# placa_v22.net
KiCad netlist of a schematic drawn in EAGLE
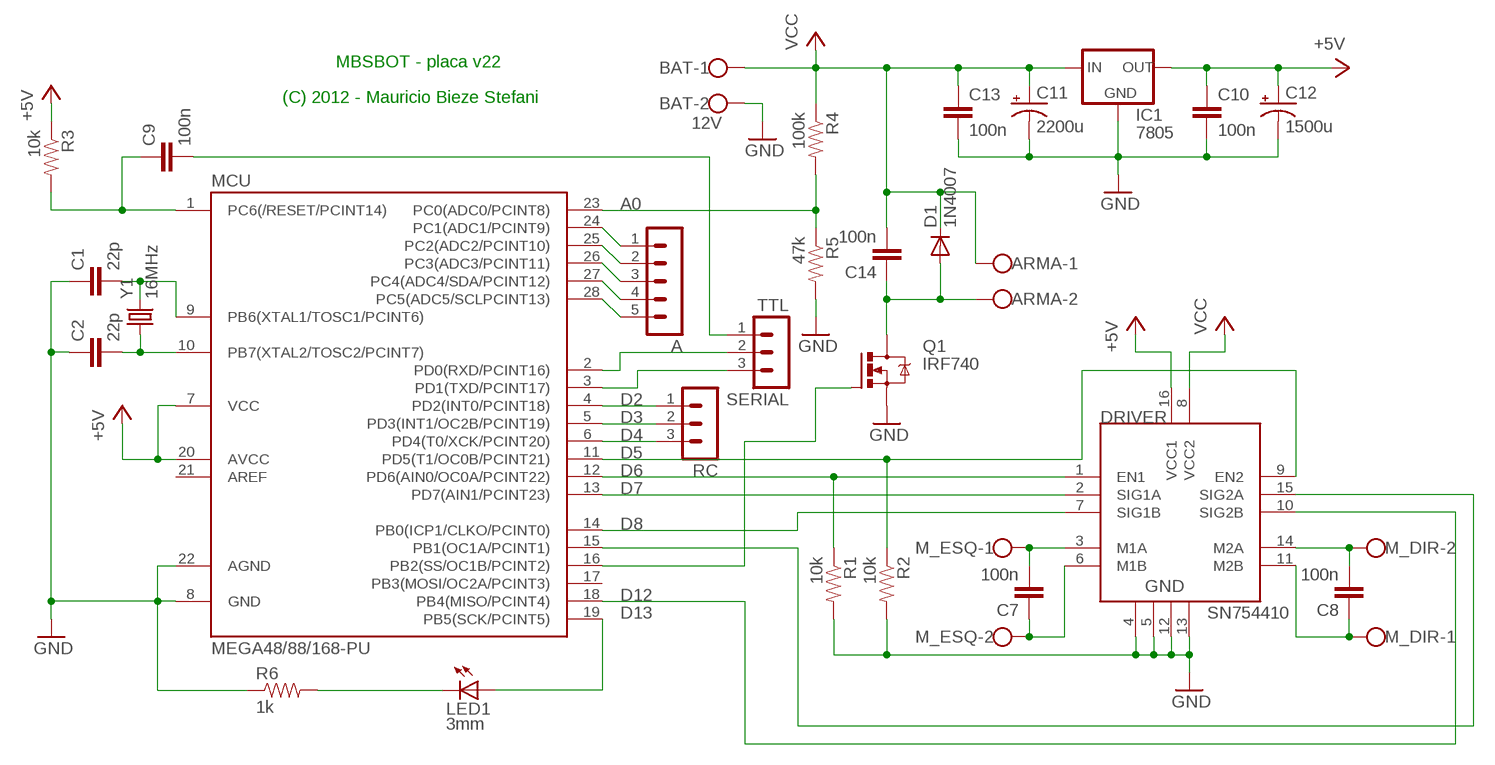
[diagram p0: schematic, sheet 1]

(export (version "E")
  (design (tool "Eeschema 10.0.6"))
  (components
    (comp (ref "A")
      (value "MA05-1")
      (footprint "eagle-import:MA05-1")
      (libsource (lib "eagle-import") (part "MA05-1"))
    )
    (comp (ref "ARMA")
      (value "W237-102")
      (footprint "eagle-import:W237-102")
      (fields (field (name "MPN") "237-102"))
      (libsource (lib "eagle-import") (part "W237-102"))
    )
    (comp (ref "BAT")
      (value "12V")
      (footprint "eagle-import:W237-102")
      (fields
        (field (name "MPN") "237-102")
        (field (name "MPN_1") "237-102")
        (field (name "OC_FARNELL") "unknown")
        (field (name "OC_NEWARK") "70K9898")
      )
      (libsource (lib "eagle-import") (part "W237-102"))
    )
    (comp (ref "C1")
      (value "22p")
      (footprint "eagle-import:CAP-PTH-SMALL-KIT")
      (libsource (lib "eagle-import") (part "CAPKIT"))
    )
    (comp (ref "C2")
      (value "22p")
      (footprint "eagle-import:CAP-PTH-SMALL-KIT")
      (libsource (lib "eagle-import") (part "CAPKIT"))
    )
    (comp (ref "C7")
      (value "100n")
      (footprint "eagle-import:CAP-PTH-5MM")
      (libsource (lib "eagle-import") (part "CAPPTH1"))
    )
    (comp (ref "C8")
      (value "100n")
      (footprint "eagle-import:CAP-PTH-5MM")
      (libsource (lib "eagle-import") (part "CAPPTH1"))
    )
    (comp (ref "C9")
      (value "100n")
      (footprint "eagle-import:CAP-PTH-5MM")
      (libsource (lib "eagle-import") (part "CAPPTH1"))
    )
    (comp (ref "C10")
      (value "100n")
      (footprint "eagle-import:CAP-PTH-5MM")
      (libsource (lib "eagle-import") (part "CAPPTH1"))
    )
    (comp (ref "C11")
      (value "2200u")
      (footprint "eagle-import:CPOL-RADIAL-100UF-25V")
      (libsource (lib "eagle-import") (part "CAP_POLPTH1"))
    )
    (comp (ref "C12")
      (value "1500u")
      (footprint "eagle-import:CPOL-RADIAL-100UF-25V")
      (libsource (lib "eagle-import") (part "CAP_POLPTH1"))
    )
    (comp (ref "C13")
      (value "100n")
      (footprint "eagle-import:CAP-PTH-5MM")
      (libsource (lib "eagle-import") (part "CAPPTH1"))
    )
    (comp (ref "C14")
      (value "100n")
      (footprint "eagle-import:CAP-PTH-5MM")
      (libsource (lib "eagle-import") (part "CAPPTH1"))
    )
    (comp (ref "D1")
      (value "1N4007")
      (footprint "eagle-import:DIODE-1N4001")
      (libsource (lib "eagle-import") (part "DIODEPTH"))
    )
    (comp (ref "DRIVER")
      (value "SN754410")
      (footprint "eagle-import:DIP16")
      (libsource (lib "eagle-import") (part "SN754410"))
    )
    (comp (ref "IC1")
      (value "7805")
      (footprint "eagle-import:78XXS")
      (libsource (lib "eagle-import") (part "78XXS"))
    )
    (comp (ref "LED1")
      (value "3mm")
      (footprint "eagle-import:LED3MM")
      (libsource (lib "eagle-import") (part "LED3MM"))
    )
    (comp (ref "MCU")
      (value "MEGA48/88/168-PU")
      (footprint "eagle-import:DIL28-3")
      (libsource (lib "eagle-import") (part "MEGA48/88/168-PU"))
    )
    (comp (ref "M_DIR")
      (value "W237-102")
      (footprint "eagle-import:W237-102")
      (fields (field (name "MPN") "237-102"))
      (libsource (lib "eagle-import") (part "W237-102"))
    )
    (comp (ref "M_ESQ")
      (value "W237-102")
      (footprint "eagle-import:W237-102")
      (fields (field (name "MPN") "237-102"))
      (libsource (lib "eagle-import") (part "W237-102"))
    )
    (comp (ref "Q1")
      (value "IRF740")
      (footprint "eagle-import:TO220BV")
      (libsource (lib "eagle-import") (part "IRF740"))
    )
    (comp (ref "R1")
      (value "10k")
      (footprint "eagle-import:AXIAL-0.5")
      (libsource (lib "eagle-import") (part "RESISTORPTH-1/2W"))
    )
    (comp (ref "R2")
      (value "10k")
      (footprint "eagle-import:AXIAL-0.5")
      (libsource (lib "eagle-import") (part "RESISTORPTH-1/2W"))
    )
    (comp (ref "R3")
      (value "10k")
      (footprint "eagle-import:AXIAL-0.5")
      (libsource (lib "eagle-import") (part "RESISTORPTH-1/2W"))
    )
    (comp (ref "R4")
      (value "100k")
      (footprint "eagle-import:AXIAL-0.5")
      (libsource (lib "eagle-import") (part "RESISTORPTH-1/2W"))
    )
    (comp (ref "R5")
      (value "47k")
      (footprint "eagle-import:AXIAL-0.5")
      (libsource (lib "eagle-import") (part "RESISTORPTH-1/2W"))
    )
    (comp (ref "R6")
      (value "1k")
      (footprint "eagle-import:AXIAL-0.3-KIT")
      (libsource (lib "eagle-import") (part "RESISTORKIT"))
    )
    (comp (ref "RC")
      (value "MA03-1")
      (footprint "eagle-import:MA03-1")
      (libsource (lib "eagle-import") (part "MA03-1"))
    )
    (comp (ref "SERIAL")
      (value "TTL")
      (footprint "eagle-import:MA03-1")
      (fields (field (name "OC_FARNELL") "unknown") (field (name "OC_NEWARK") "unknown"))
      (libsource (lib "eagle-import") (part "MA03-1"))
    )
    (comp (ref "Y1")
      (value "16MHz")
      (footprint "eagle-import:HC49US")
      (libsource (lib "eagle-import") (part "CRYSTALHC49US"))
    )
  )
  (nets
    (net (code "1") (name "+5V") (class "Default")
      (node (ref "C10") (pin "1") (pinfunction "1_1") (pintype "passive"))
      (node (ref "C12") (pin "1") (pinfunction "+_1") (pintype "passive"))
      (node (ref "DRIVER") (pin "16") (pinfunction "VCC1_16") (pintype "power_in"))
      (node (ref "IC1") (pin "OUT") (pinfunction "OUT_OUT") (pintype "passive"))
      (node (ref "MCU") (pin "20") (pinfunction "AVCC_20") (pintype "passive"))
      (node (ref "MCU") (pin "7") (pinfunction "VCC_7") (pintype "power_in"))
      (node (ref "R3") (pin "P$1") (pinfunction "1_P$1") (pintype "passive"))
    )
    (net (code "2") (name "/A0") (class "Default")
      (node (ref "MCU") (pin "23") (pinfunction "PC0(ADC0/PCINT8)_23") (pintype "bidirectional"))
      (node (ref "R4") (pin "P$2") (pinfunction "2_P$2") (pintype "passive"))
      (node (ref "R5") (pin "P$1") (pinfunction "1_P$1") (pintype "passive"))
    )
    (net (code "3") (name "/D2") (class "Default")
      (node (ref "MCU") (pin "4") (pinfunction "PD2(INT0/PCINT18)_4") (pintype "bidirectional"))
      (node (ref "RC") (pin "1") (pinfunction "1_1") (pintype "passive"))
    )
    (net (code "4") (name "/D3") (class "Default")
      (node (ref "MCU") (pin "5") (pinfunction "PD3(INT1/OC2B/PCINT19)_5") (pintype "bidirectional"))
      (node (ref "RC") (pin "2") (pinfunction "2_2") (pintype "passive"))
    )
    (net (code "5") (name "/D4") (class "Default")
      (node (ref "MCU") (pin "6") (pinfunction "PD4(T0/XCK/PCINT20)_6") (pintype "bidirectional"))
      (node (ref "RC") (pin "3") (pinfunction "3_3") (pintype "passive"))
    )
    (net (code "6") (name "/D5") (class "Default")
      (node (ref "DRIVER") (pin "9") (pinfunction "EN2_9") (pintype "bidirectional"))
      (node (ref "MCU") (pin "11") (pinfunction "PD5(T1/OC0B/PCINT21)_11") (pintype "bidirectional"))
      (node (ref "R2") (pin "P$1") (pinfunction "1_P$1") (pintype "passive"))
    )
    (net (code "7") (name "/D6") (class "Default")
      (node (ref "DRIVER") (pin "1") (pinfunction "EN1_1") (pintype "bidirectional"))
      (node (ref "MCU") (pin "12") (pinfunction "PD6(AIN0/OC0A/PCINT22)_12") (pintype "bidirectional"))
      (node (ref "R1") (pin "P$1") (pinfunction "1_P$1") (pintype "passive"))
    )
    (net (code "8") (name "/D7") (class "Default")
      (node (ref "DRIVER") (pin "2") (pinfunction "SIG1A_2") (pintype "bidirectional"))
      (node (ref "MCU") (pin "13") (pinfunction "PD7(AIN1/PCINT23)_13") (pintype "bidirectional"))
    )
    (net (code "9") (name "/D8") (class "Default")
      (node (ref "DRIVER") (pin "7") (pinfunction "SIG1B_7") (pintype "bidirectional"))
      (node (ref "MCU") (pin "14") (pinfunction "PB0(ICP1/CLKO/PCINT0)_14") (pintype "bidirectional"))
    )
    (net (code "10") (name "/D12") (class "Default")
      (node (ref "DRIVER") (pin "10") (pinfunction "SIG2B_10") (pintype "bidirectional"))
      (node (ref "MCU") (pin "18") (pinfunction "PB4(MISO/PCINT4)_18") (pintype "bidirectional"))
    )
    (net (code "11") (name "/D13") (class "Default")
      (node (ref "LED1") (pin "A") (pinfunction "A_A") (pintype "passive"))
      (node (ref "MCU") (pin "19") (pinfunction "PB5(SCK/PCINT5)_19") (pintype "bidirectional"))
    )
    (net (code "12") (name "GND") (class "Default")
      (node (ref "BAT") (pin "2") (pinfunction "KL_2") (pintype "passive"))
      (node (ref "C1") (pin "1") (pinfunction "1_1") (pintype "passive"))
      (node (ref "C10") (pin "2") (pinfunction "2_2") (pintype "passive"))
      (node (ref "C11") (pin "2") (pinfunction "-_2") (pintype "passive"))
      (node (ref "C12") (pin "2") (pinfunction "-_2") (pintype "passive"))
      (node (ref "C13") (pin "2") (pinfunction "2_2") (pintype "passive"))
      (node (ref "C2") (pin "1") (pinfunction "1_1") (pintype "passive"))
      (node (ref "DRIVER") (pin "12") (pinfunction "P12_12") (pintype "power_in"))
      (node (ref "DRIVER") (pin "13") (pinfunction "P13_13") (pintype "power_in"))
      (node (ref "DRIVER") (pin "4") (pinfunction "P4_4") (pintype "power_in"))
      (node (ref "DRIVER") (pin "5") (pinfunction "P5_5") (pintype "power_in"))
      (node (ref "IC1") (pin "GND") (pinfunction "GND_GND") (pintype "input"))
      (node (ref "MCU") (pin "22") (pinfunction "AGND_22") (pintype "power_in"))
      (node (ref "MCU") (pin "8") (pinfunction "GND_8") (pintype "power_in"))
      (node (ref "Q1") (pin "S") (pinfunction "S_S") (pintype "passive"))
      (node (ref "R1") (pin "P$2") (pinfunction "2_P$2") (pintype "passive"))
      (node (ref "R2") (pin "P$2") (pinfunction "2_P$2") (pintype "passive"))
      (node (ref "R5") (pin "P$2") (pinfunction "2_P$2") (pintype "passive"))
      (node (ref "R6") (pin "P$1") (pinfunction "1_P$1") (pintype "passive"))
    )
    (net (code "13") (name "Net-(ARMAB-KL)") (class "Default")
      (node (ref "ARMA") (pin "2") (pinfunction "KL_2") (pintype "passive"))
      (node (ref "C14") (pin "1") (pinfunction "1_1") (pintype "passive"))
      (node (ref "D1") (pin "A") (pinfunction "A_A") (pintype "passive"))
      (node (ref "Q1") (pin "D") (pinfunction "D_D") (pintype "passive"))
    )
    (net (code "14") (name "Net-(C9-Pad2)") (class "Default")
      (node (ref "C9") (pin "2") (pinfunction "2_2") (pintype "passive"))
      (node (ref "SERIAL") (pin "1") (pinfunction "1_1") (pintype "passive"))
    )
    (net (code "15") (name "Net-(DRIVER-M1A)") (class "Default")
      (node (ref "C7") (pin "2") (pinfunction "2_2") (pintype "passive"))
      (node (ref "DRIVER") (pin "3") (pinfunction "M1A_3") (pintype "bidirectional"))
      (node (ref "M_ESQ") (pin "1") (pinfunction "KL_1") (pintype "passive"))
    )
    (net (code "16") (name "Net-(DRIVER-M1B)") (class "Default")
      (node (ref "C7") (pin "1") (pinfunction "1_1") (pintype "passive"))
      (node (ref "DRIVER") (pin "6") (pinfunction "M1B_6") (pintype "bidirectional"))
      (node (ref "M_ESQ") (pin "2") (pinfunction "KL_2") (pintype "passive"))
    )
    (net (code "17") (name "Net-(DRIVER-M2A)") (class "Default")
      (node (ref "C8") (pin "2") (pinfunction "2_2") (pintype "passive"))
      (node (ref "DRIVER") (pin "14") (pinfunction "M2A_14") (pintype "bidirectional"))
      (node (ref "M_DIR") (pin "2") (pinfunction "KL_2") (pintype "passive"))
    )
    (net (code "18") (name "Net-(DRIVER-M2B)") (class "Default")
      (node (ref "C8") (pin "1") (pinfunction "1_1") (pintype "passive"))
      (node (ref "DRIVER") (pin "11") (pinfunction "M2B_11") (pintype "bidirectional"))
      (node (ref "M_DIR") (pin "1") (pinfunction "KL_1") (pintype "passive"))
    )
    (net (code "19") (name "Net-(DRIVER-SIG2A)") (class "Default")
      (node (ref "DRIVER") (pin "15") (pinfunction "SIG2A_15") (pintype "bidirectional"))
      (node (ref "MCU") (pin "15") (pinfunction "PB1(OC1A/PCINT1)_15") (pintype "bidirectional"))
    )
    (net (code "20") (name "Net-(LED1-C)") (class "Default")
      (node (ref "LED1") (pin "K") (pinfunction "C_K") (pintype "passive"))
      (node (ref "R6") (pin "P$2") (pinfunction "2_P$2") (pintype "passive"))
    )
    (net (code "21") (name "Net-(MCU-PB2(SS{slash}OC1B{slash}PCINT2))") (class "Default")
      (node (ref "MCU") (pin "16") (pinfunction "PB2(SS/OC1B/PCINT2)_16") (pintype "bidirectional"))
      (node (ref "Q1") (pin "G") (pinfunction "G_G") (pintype "passive"))
    )
    (net (code "22") (name "Net-(MCU-PB6(XTAL1{slash}TOSC1{slash}PCINT6))") (class "Default")
      (node (ref "C1") (pin "2") (pinfunction "2_2") (pintype "passive"))
      (node (ref "MCU") (pin "9") (pinfunction "PB6(XTAL1/TOSC1/PCINT6)_9") (pintype "bidirectional"))
      (node (ref "Y1") (pin "2") (pinfunction "2_2") (pintype "passive"))
    )
    (net (code "23") (name "Net-(MCU-PB7(XTAL2{slash}TOSC2{slash}PCINT7))") (class "Default")
      (node (ref "C2") (pin "2") (pinfunction "2_2") (pintype "passive"))
      (node (ref "MCU") (pin "10") (pinfunction "PB7(XTAL2/TOSC2/PCINT7)_10") (pintype "bidirectional"))
      (node (ref "Y1") (pin "1") (pinfunction "1_1") (pintype "passive"))
    )
    (net (code "24") (name "Net-(MCU-PC1(ADC1{slash}PCINT9))") (class "Default")
      (node (ref "A") (pin "1") (pinfunction "1_1") (pintype "passive"))
      (node (ref "MCU") (pin "24") (pinfunction "PC1(ADC1/PCINT9)_24") (pintype "bidirectional"))
    )
    (net (code "25") (name "Net-(MCU-PC2(ADC2{slash}PCINT10))") (class "Default")
      (node (ref "A") (pin "2") (pinfunction "2_2") (pintype "passive"))
      (node (ref "MCU") (pin "25") (pinfunction "PC2(ADC2/PCINT10)_25") (pintype "bidirectional"))
    )
    (net (code "26") (name "Net-(MCU-PC3(ADC3{slash}PCINT11))") (class "Default")
      (node (ref "A") (pin "3") (pinfunction "3_3") (pintype "passive"))
      (node (ref "MCU") (pin "26") (pinfunction "PC3(ADC3/PCINT11)_26") (pintype "bidirectional"))
    )
    (net (code "27") (name "Net-(MCU-PC4(ADC4{slash}SDA{slash}PCINT12))") (class "Default")
      (node (ref "A") (pin "4") (pinfunction "4_4") (pintype "passive"))
      (node (ref "MCU") (pin "27") (pinfunction "PC4(ADC4/SDA/PCINT12)_27") (pintype "bidirectional"))
    )
    (net (code "28") (name "Net-(MCU-PC5(ADC5{slash}SCLPCINT13))") (class "Default")
      (node (ref "A") (pin "5") (pinfunction "5_5") (pintype "passive"))
      (node (ref "MCU") (pin "28") (pinfunction "PC5(ADC5/SCLPCINT13)_28") (pintype "bidirectional"))
    )
    (net (code "29") (name "Net-(MCU-PC6({slash}RESET{slash}PCINT14))") (class "Default")
      (node (ref "C9") (pin "1") (pinfunction "1_1") (pintype "passive"))
      (node (ref "MCU") (pin "1") (pinfunction "PC6(/RESET/PCINT14)_1") (pintype "bidirectional"))
      (node (ref "R3") (pin "P$2") (pinfunction "2_P$2") (pintype "passive"))
    )
    (net (code "30") (name "Net-(MCU-PD0(RXD{slash}PCINT16))") (class "Default")
      (node (ref "MCU") (pin "2") (pinfunction "PD0(RXD/PCINT16)_2") (pintype "bidirectional"))
      (node (ref "SERIAL") (pin "2") (pinfunction "2_2") (pintype "passive"))
    )
    (net (code "31") (name "Net-(MCU-PD1(TXD{slash}PCINT17))") (class "Default")
      (node (ref "MCU") (pin "3") (pinfunction "PD1(TXD/PCINT17)_3") (pintype "bidirectional"))
      (node (ref "SERIAL") (pin "3") (pinfunction "3_3") (pintype "passive"))
    )
    (net (code "32") (name "VCC") (class "Default")
      (node (ref "ARMA") (pin "1") (pinfunction "KL_1") (pintype "passive"))
      (node (ref "BAT") (pin "1") (pinfunction "KL_1") (pintype "passive"))
      (node (ref "C11") (pin "1") (pinfunction "+_1") (pintype "passive"))
      (node (ref "C13") (pin "1") (pinfunction "1_1") (pintype "passive"))
      (node (ref "C14") (pin "2") (pinfunction "2_2") (pintype "passive"))
      (node (ref "D1") (pin "C") (pinfunction "C_C") (pintype "passive"))
      (node (ref "DRIVER") (pin "8") (pinfunction "VCC2_8") (pintype "power_in"))
      (node (ref "IC1") (pin "IN") (pinfunction "IN_IN") (pintype "input"))
      (node (ref "R4") (pin "P$1") (pinfunction "1_P$1") (pintype "passive"))
    )
    (net (code "33") (name "unconnected-(MCU-AREF-Pad21)") (class "Default")
      (node (ref "MCU") (pin "21") (pinfunction "AREF_21") (pintype "passive"))
    )
    (net (code "34") (name "unconnected-(MCU-PB3(MOSI{slash}OC2A{slash}PCINT3)-Pad17)") (class "Default")
      (node (ref "MCU") (pin "17") (pinfunction "PB3(MOSI/OC2A/PCINT3)_17") (pintype "bidirectional"))
    )
  )
)
